# inout.net
KiCad netlist of a schematic drawn in Altium Designer
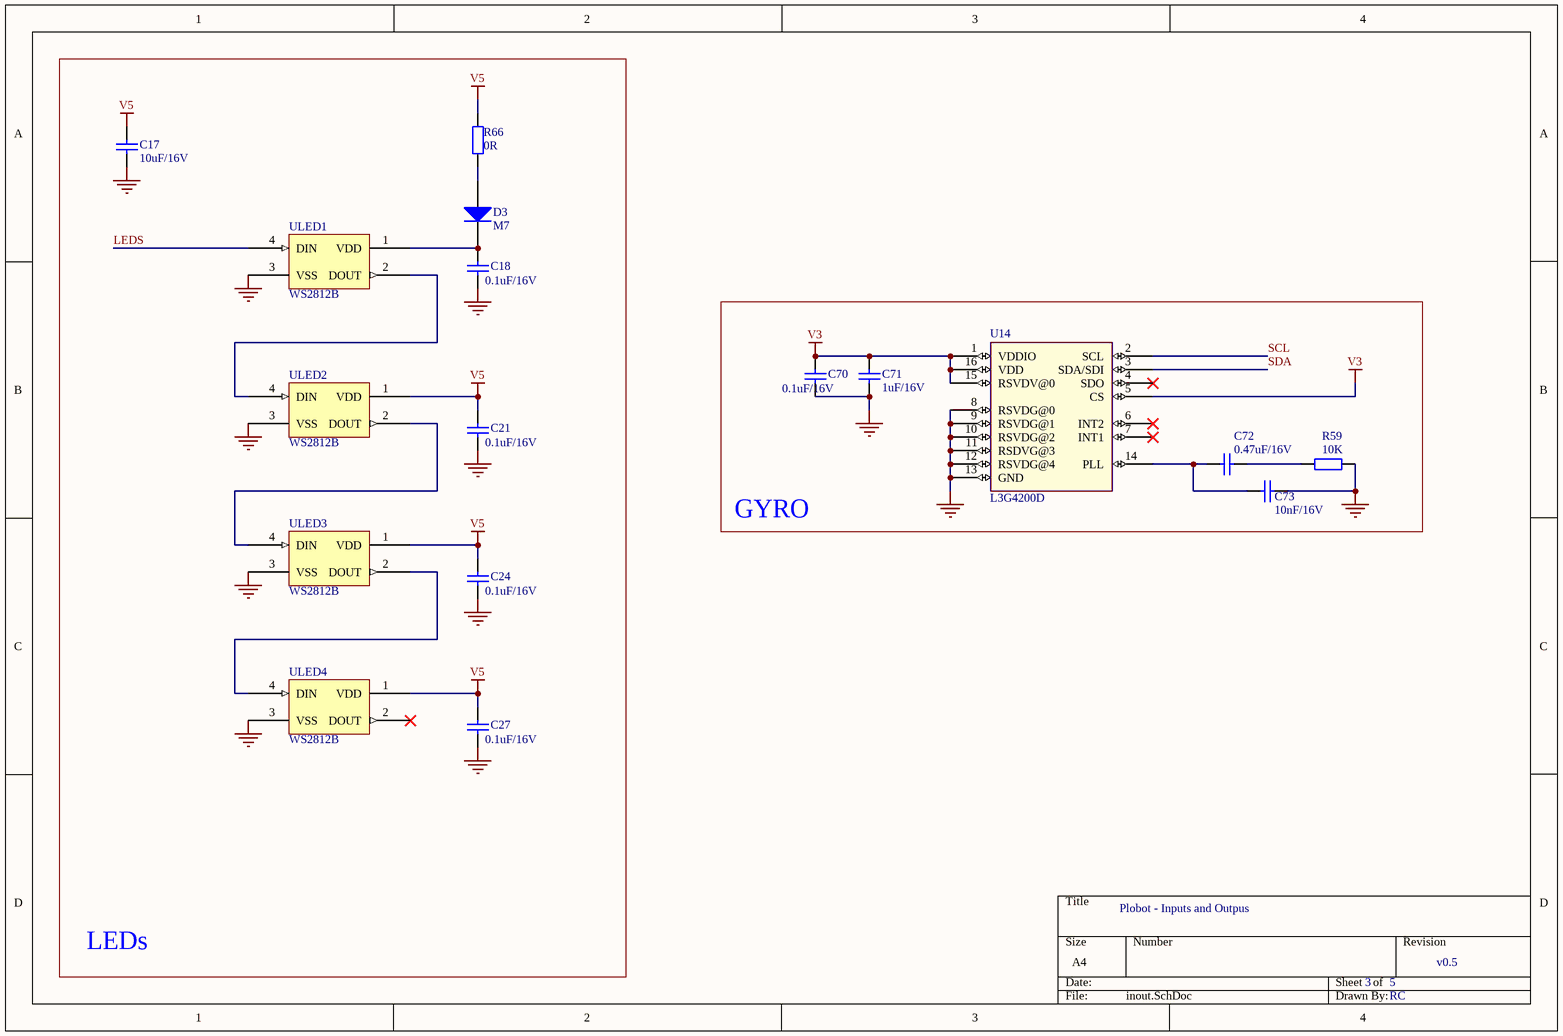
[diagram p0: inout.SchDoc]

(export (version "E")
  (design (tool "Eeschema 10.0.6"))
  (components
    (comp (ref "C17")
      (value "10uF/16V")
      (footprint "CAPC1608N")
      (description "Capacitor")
      (fields (field (name "PUBLISHER") "Altium Limited"))
      (libsource (lib "") (part "Cap_2_1"))
    )
    (comp (ref "C18")
      (value "0.1uF/16V")
      (footprint "CAPC1608N")
      (description "Capacitor")
      (fields (field (name "PUBLISHER") "Altium Limited"))
      (libsource (lib "*") (part "Cap"))
    )
    (comp (ref "C21")
      (value "0.1uF/16V")
      (footprint "CAPC1608N")
      (description "Capacitor")
      (fields (field (name "PUBLISHER") "Altium Limited"))
      (libsource (lib "*") (part "Cap"))
    )
    (comp (ref "C24")
      (value "0.1uF/16V")
      (footprint "CAPC1608N")
      (description "Capacitor")
      (fields (field (name "PUBLISHER") "Altium Limited"))
      (libsource (lib "*") (part "Cap"))
    )
    (comp (ref "C27")
      (value "0.1uF/16V")
      (footprint "CAPC1608N")
      (description "Capacitor")
      (fields (field (name "PUBLISHER") "Altium Limited"))
      (libsource (lib "*") (part "Cap"))
    )
    (comp (ref "C70")
      (value "0.1uF/16V")
      (footprint "CAPC1608N")
      (description "Capacitor")
      (libsource (lib "*") (part "Cap"))
    )
    (comp (ref "C71")
      (value "1uF/16V")
      (footprint "CAPC1608N")
      (description "Capacitor")
      (libsource (lib "") (part "Cap_2_1"))
    )
    (comp (ref "C72")
      (value "0.47uF/16V")
      (footprint "CAPC1608N")
      (description "Capacitor")
      (libsource (lib "main_pcb") (part "Cap_2"))
    )
    (comp (ref "C73")
      (value "10nF/16V")
      (footprint "CAPC1608N")
      (description "Capacitor")
      (libsource (lib "main_pcb") (part "Cap_2"))
    )
    (comp (ref "D3")
      (value "M7")
      (footprint "SMA")
      (description "Default Diode")
      (fields (field (name "PUBLISHER") "Altium Limited"))
      (libsource (lib "Miscellaneous Devices") (part "Diode"))
    )
    (comp (ref "R59")
      (value "10K")
      (footprint "RESC1608N")
      (description "Resistor")
      (libsource (lib "*") (part "Res2"))
    )
    (comp (ref "R66")
      (value "0R")
      (footprint "RESC1608N")
      (description "Resistor")
      (fields (field (name "PUBLISHER") "Altium Limited"))
      (libsource (lib "*") (part "Res2"))
    )
    (comp (ref "U14")
      (value "L3G4200D")
      (footprint "LGA16-4X4")
      (description "L3G4200D Series 2.4 - 3.6 V Three-axis Angular Rate MEMS Motion Sensor - LGA-16")
      (libsource (lib "L3G4200D") (part "L3G4200D"))
    )
    (comp (ref "ULED1")
      (value "WS2812B")
      (footprint "plobot_review:WS2812B")
      (libsource (lib "components") (part "WS2812B"))
    )
    (comp (ref "ULED2")
      (value "WS2812B")
      (footprint "plobot_review:WS2812B")
      (libsource (lib "components") (part "WS2812B"))
    )
    (comp (ref "ULED3")
      (value "WS2812B")
      (footprint "plobot_review:WS2812B")
      (libsource (lib "components") (part "WS2812B"))
    )
    (comp (ref "ULED4")
      (value "WS2812B")
      (footprint "plobot_review:WS2812B")
      (libsource (lib "components") (part "WS2812B"))
    )
  )
  (nets
    (net (code "1") (name "/LEDS") (class "Default")
      (node (ref "ULED1") (pin "4") (pinfunction "DIN_4") (pintype "input"))
    )
    (net (code "2") (name "/SCL") (class "Default")
      (node (ref "U14") (pin "2") (pinfunction "SCL_2") (pintype "bidirectional"))
    )
    (net (code "3") (name "/SDA") (class "Default")
      (node (ref "U14") (pin "3") (pinfunction "SDA/SDI_3") (pintype "bidirectional"))
    )
    (net (code "4") (name "GND") (class "Default")
      (node (ref "C17") (pin "2") (pinfunction "2_2") (pintype "passive"))
      (node (ref "C18") (pin "2") (pinfunction "2_2") (pintype "passive"))
      (node (ref "C21") (pin "2") (pinfunction "2_2") (pintype "passive"))
      (node (ref "C24") (pin "2") (pinfunction "2_2") (pintype "passive"))
      (node (ref "C27") (pin "2") (pinfunction "2_2") (pintype "passive"))
      (node (ref "C70") (pin "2") (pinfunction "2_2") (pintype "passive"))
      (node (ref "C71") (pin "2") (pinfunction "2_2") (pintype "passive"))
      (node (ref "C73") (pin "2") (pinfunction "2_2") (pintype "passive"))
      (node (ref "R59") (pin "2") (pinfunction "2_2") (pintype "passive"))
      (node (ref "U14") (pin "10") (pinfunction "RSVDG@2_10") (pintype "bidirectional"))
      (node (ref "U14") (pin "11") (pinfunction "RSDVG@3_11") (pintype "bidirectional"))
      (node (ref "U14") (pin "12") (pinfunction "RSVDG@4_12") (pintype "bidirectional"))
      (node (ref "U14") (pin "13") (pinfunction "GND_13") (pintype "bidirectional"))
      (node (ref "U14") (pin "8") (pinfunction "RSVDG@0_8") (pintype "bidirectional"))
      (node (ref "U14") (pin "9") (pinfunction "RSVDG@1_9") (pintype "bidirectional"))
      (node (ref "ULED1") (pin "3") (pinfunction "VSS_3") (pintype "power_in"))
      (node (ref "ULED2") (pin "3") (pinfunction "VSS_3") (pintype "power_in"))
      (node (ref "ULED3") (pin "3") (pinfunction "VSS_3") (pintype "power_in"))
      (node (ref "ULED4") (pin "3") (pinfunction "VSS_3") (pintype "power_in"))
    )
    (net (code "5") (name "Net-(C72-Pad2)") (class "Default")
      (node (ref "C72") (pin "2") (pinfunction "2_2") (pintype "passive"))
      (node (ref "R59") (pin "1") (pinfunction "1_1") (pintype "passive"))
    )
    (net (code "6") (name "Net-(D3-A)") (class "Default")
      (node (ref "D3") (pin "1") (pinfunction "A_1") (pintype "passive"))
      (node (ref "R66") (pin "1") (pinfunction "1_1") (pintype "passive"))
    )
    (net (code "7") (name "Net-(D3-K)") (class "Default")
      (node (ref "C18") (pin "1") (pinfunction "1_1") (pintype "passive"))
      (node (ref "D3") (pin "2") (pinfunction "K_2") (pintype "passive"))
      (node (ref "ULED1") (pin "1") (pinfunction "VDD_1") (pintype "power_in"))
    )
    (net (code "8") (name "Net-(U14-PLL)") (class "Default")
      (node (ref "C72") (pin "1") (pinfunction "1_1") (pintype "passive"))
      (node (ref "C73") (pin "1") (pinfunction "1_1") (pintype "passive"))
      (node (ref "U14") (pin "14") (pinfunction "PLL_14") (pintype "bidirectional"))
    )
    (net (code "9") (name "Net-(ULED1-DOUT)") (class "Default")
      (node (ref "ULED1") (pin "2") (pinfunction "DOUT_2") (pintype "output"))
      (node (ref "ULED2") (pin "4") (pinfunction "DIN_4") (pintype "input"))
    )
    (net (code "10") (name "Net-(ULED2-DOUT)") (class "Default")
      (node (ref "ULED2") (pin "2") (pinfunction "DOUT_2") (pintype "output"))
      (node (ref "ULED3") (pin "4") (pinfunction "DIN_4") (pintype "input"))
    )
    (net (code "11") (name "Net-(ULED3-DOUT)") (class "Default")
      (node (ref "ULED3") (pin "2") (pinfunction "DOUT_2") (pintype "output"))
      (node (ref "ULED4") (pin "4") (pinfunction "DIN_4") (pintype "input"))
    )
    (net (code "12") (name "V3") (class "Default")
      (node (ref "C70") (pin "1") (pinfunction "1_1") (pintype "passive"))
      (node (ref "C71") (pin "1") (pinfunction "1_1") (pintype "passive"))
      (node (ref "U14") (pin "1") (pinfunction "VDDIO_1") (pintype "bidirectional"))
      (node (ref "U14") (pin "15") (pinfunction "RSVDV@0_15") (pintype "bidirectional"))
      (node (ref "U14") (pin "16") (pinfunction "VDD_16") (pintype "bidirectional"))
      (node (ref "U14") (pin "5") (pinfunction "CS_5") (pintype "bidirectional"))
    )
    (net (code "13") (name "V5") (class "Default")
      (node (ref "C17") (pin "1") (pinfunction "1_1") (pintype "passive"))
      (node (ref "C21") (pin "1") (pinfunction "1_1") (pintype "passive"))
      (node (ref "C24") (pin "1") (pinfunction "1_1") (pintype "passive"))
      (node (ref "C27") (pin "1") (pinfunction "1_1") (pintype "passive"))
      (node (ref "R66") (pin "2") (pinfunction "2_2") (pintype "passive"))
      (node (ref "ULED2") (pin "1") (pinfunction "VDD_1") (pintype "power_in"))
      (node (ref "ULED3") (pin "1") (pinfunction "VDD_1") (pintype "power_in"))
      (node (ref "ULED4") (pin "1") (pinfunction "VDD_1") (pintype "power_in"))
    )
    (net (code "14") (name "unconnected-(U14-INT1-Pad7)") (class "Default")
      (node (ref "U14") (pin "7") (pinfunction "INT1_7") (pintype "bidirectional+no_connect"))
    )
    (net (code "15") (name "unconnected-(U14-INT2-Pad6)") (class "Default")
      (node (ref "U14") (pin "6") (pinfunction "INT2_6") (pintype "bidirectional+no_connect"))
    )
    (net (code "16") (name "unconnected-(U14-SDO-Pad4)") (class "Default")
      (node (ref "U14") (pin "4") (pinfunction "SDO_4") (pintype "bidirectional+no_connect"))
    )
    (net (code "17") (name "unconnected-(ULED4-DOUT-Pad2)") (class "Default")
      (node (ref "ULED4") (pin "2") (pinfunction "DOUT_2") (pintype "output+no_connect"))
    )
  )
)
